# IRF530N_MOS_Amplifier.net
KiCad netlist of a schematic drawn in Altium Designer
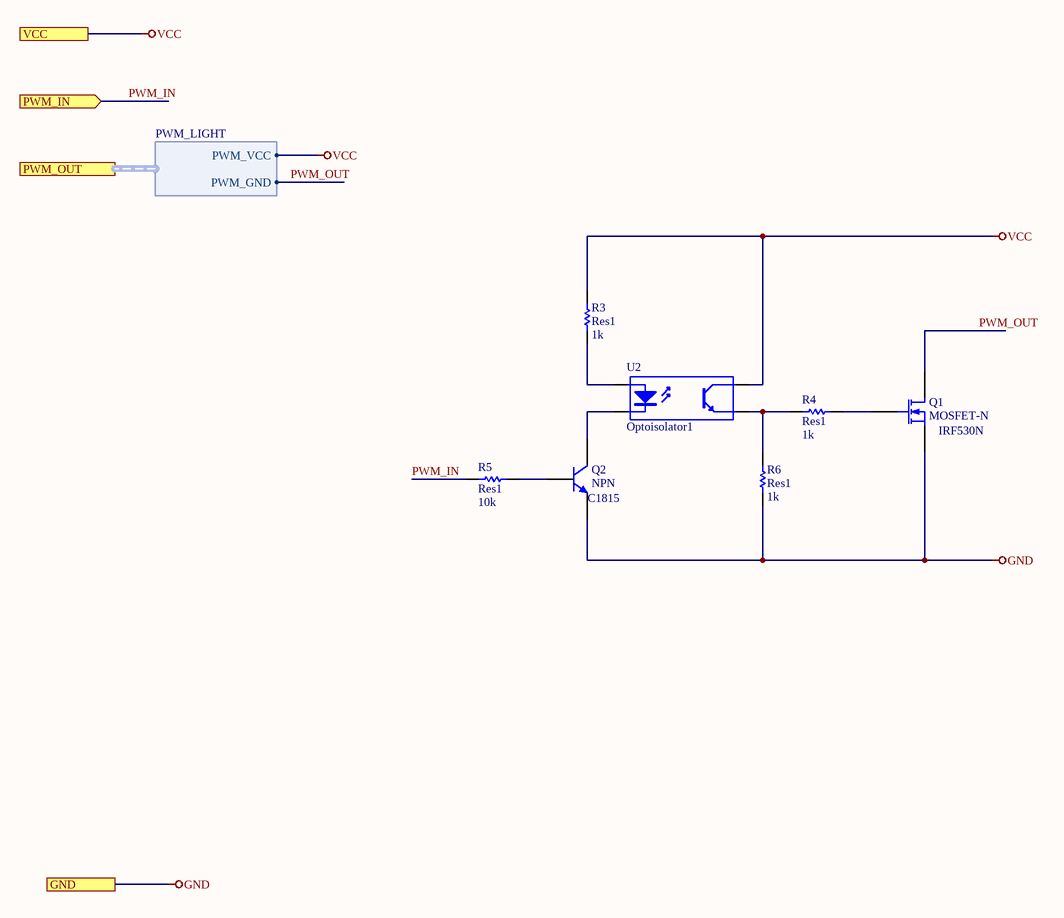
[diagram p0: IRF530N_MOS_Amplifier.SchDoc]

(export (version "E")
  (design (tool "Eeschema 10.0.6"))
  (components
    (comp (ref "Q1")
      (value "MOSFET-N")
      (footprint "TO-263")
      (description "N-Channel MOSFET")
      (fields (field (name "NAME") "IRF530N") (field (name "PUBLISHER") "Altium Limited"))
      (libsource (lib "Integrated_Library") (part "MOSFET-N"))
    )
    (comp (ref "Q2")
      (value "NPN")
      (footprint "SOT-23")
      (description "NPN Bipolar Transistor")
      (fields (field (name "NAME") "C1815") (field (name "PUBLISHER") "Altium Limited"))
      (libsource (lib "Integrated_Library") (part "NPN"))
    )
    (comp (ref "R3")
      (value "Res1")
      (footprint "R0805")
      (description "Resistor")
      (fields (field (name "ALTIUM_VALUE") "1k"))
      (libsource (lib "Integrated_Library") (part "Res1"))
    )
    (comp (ref "R4")
      (value "Res1")
      (footprint "R0805")
      (description "Resistor")
      (fields (field (name "ALTIUM_VALUE") "1k"))
      (libsource (lib "Integrated_Library") (part "Res1"))
    )
    (comp (ref "R5")
      (value "Res1")
      (footprint "R0805")
      (description "Resistor")
      (fields (field (name "ALTIUM_VALUE") "10k"))
      (libsource (lib "Integrated_Library") (part "Res1"))
    )
    (comp (ref "R6")
      (value "Res1")
      (footprint "R0805")
      (description "Resistor")
      (fields (field (name "ALTIUM_VALUE") "1k"))
      (libsource (lib "Integrated_Library") (part "Res1"))
    )
    (comp (ref "U2")
      (value "Optoisolator1")
      (footprint "DIP_4")
      (description "4-Pin Phototransistor Optocoupler")
      (fields (field (name "PUBLISHER") "Altium Limited"))
      (libsource (lib "Integrated_Library") (part "Optoisolator1"))
    )
  )
  (nets
    (net (code "2") (name "/PWM_IN") (class "Default")
      (node (ref "R5") (pin "1") (pinfunction "1_1") (pintype "passive"))
    )
    (net (code "3") (name "/PWM_OUT") (class "Default")
      (node (ref "Q1") (pin "2") (pinfunction "D_2") (pintype "passive"))
    )
    (net (code "5") (name "GND") (class "Default")
      (node (ref "Q1") (pin "3") (pinfunction "S_3") (pintype "passive"))
      (node (ref "Q2") (pin "3") (pinfunction "E_3") (pintype "passive"))
      (node (ref "R6") (pin "1") (pinfunction "1_1") (pintype "passive"))
    )
    (net (code "6") (name "Net-(Q1-G)") (class "Default")
      (node (ref "Q1") (pin "1") (pinfunction "G_1") (pintype "passive"))
      (node (ref "R4") (pin "1") (pinfunction "1_1") (pintype "passive"))
    )
    (net (code "7") (name "Net-(Q2-B)") (class "Default")
      (node (ref "Q2") (pin "2") (pinfunction "B_2") (pintype "passive"))
      (node (ref "R5") (pin "2") (pinfunction "2_2") (pintype "passive"))
    )
    (net (code "8") (name "Net-(Q2-C)") (class "Default")
      (node (ref "Q2") (pin "1") (pinfunction "C_1") (pintype "passive"))
      (node (ref "U2") (pin "2") (pinfunction "K_2") (pintype "passive"))
    )
    (net (code "9") (name "Net-(U2-A)") (class "Default")
      (node (ref "R3") (pin "1") (pinfunction "1_1") (pintype "passive"))
      (node (ref "U2") (pin "1") (pinfunction "A_1") (pintype "passive"))
    )
    (net (code "10") (name "Net-(U2-E)") (class "Default")
      (node (ref "R4") (pin "2") (pinfunction "2_2") (pintype "passive"))
      (node (ref "R6") (pin "2") (pinfunction "2_2") (pintype "passive"))
      (node (ref "U2") (pin "3") (pinfunction "E_3") (pintype "passive"))
    )
    (net (code "11") (name "VCC") (class "Default")
      (node (ref "R3") (pin "2") (pinfunction "2_2") (pintype "passive"))
      (node (ref "U2") (pin "4") (pinfunction "C_4") (pintype "passive"))
    )
  )
)
